# schematic.net
KiCad netlist of a schematic drawn in Altium Designer
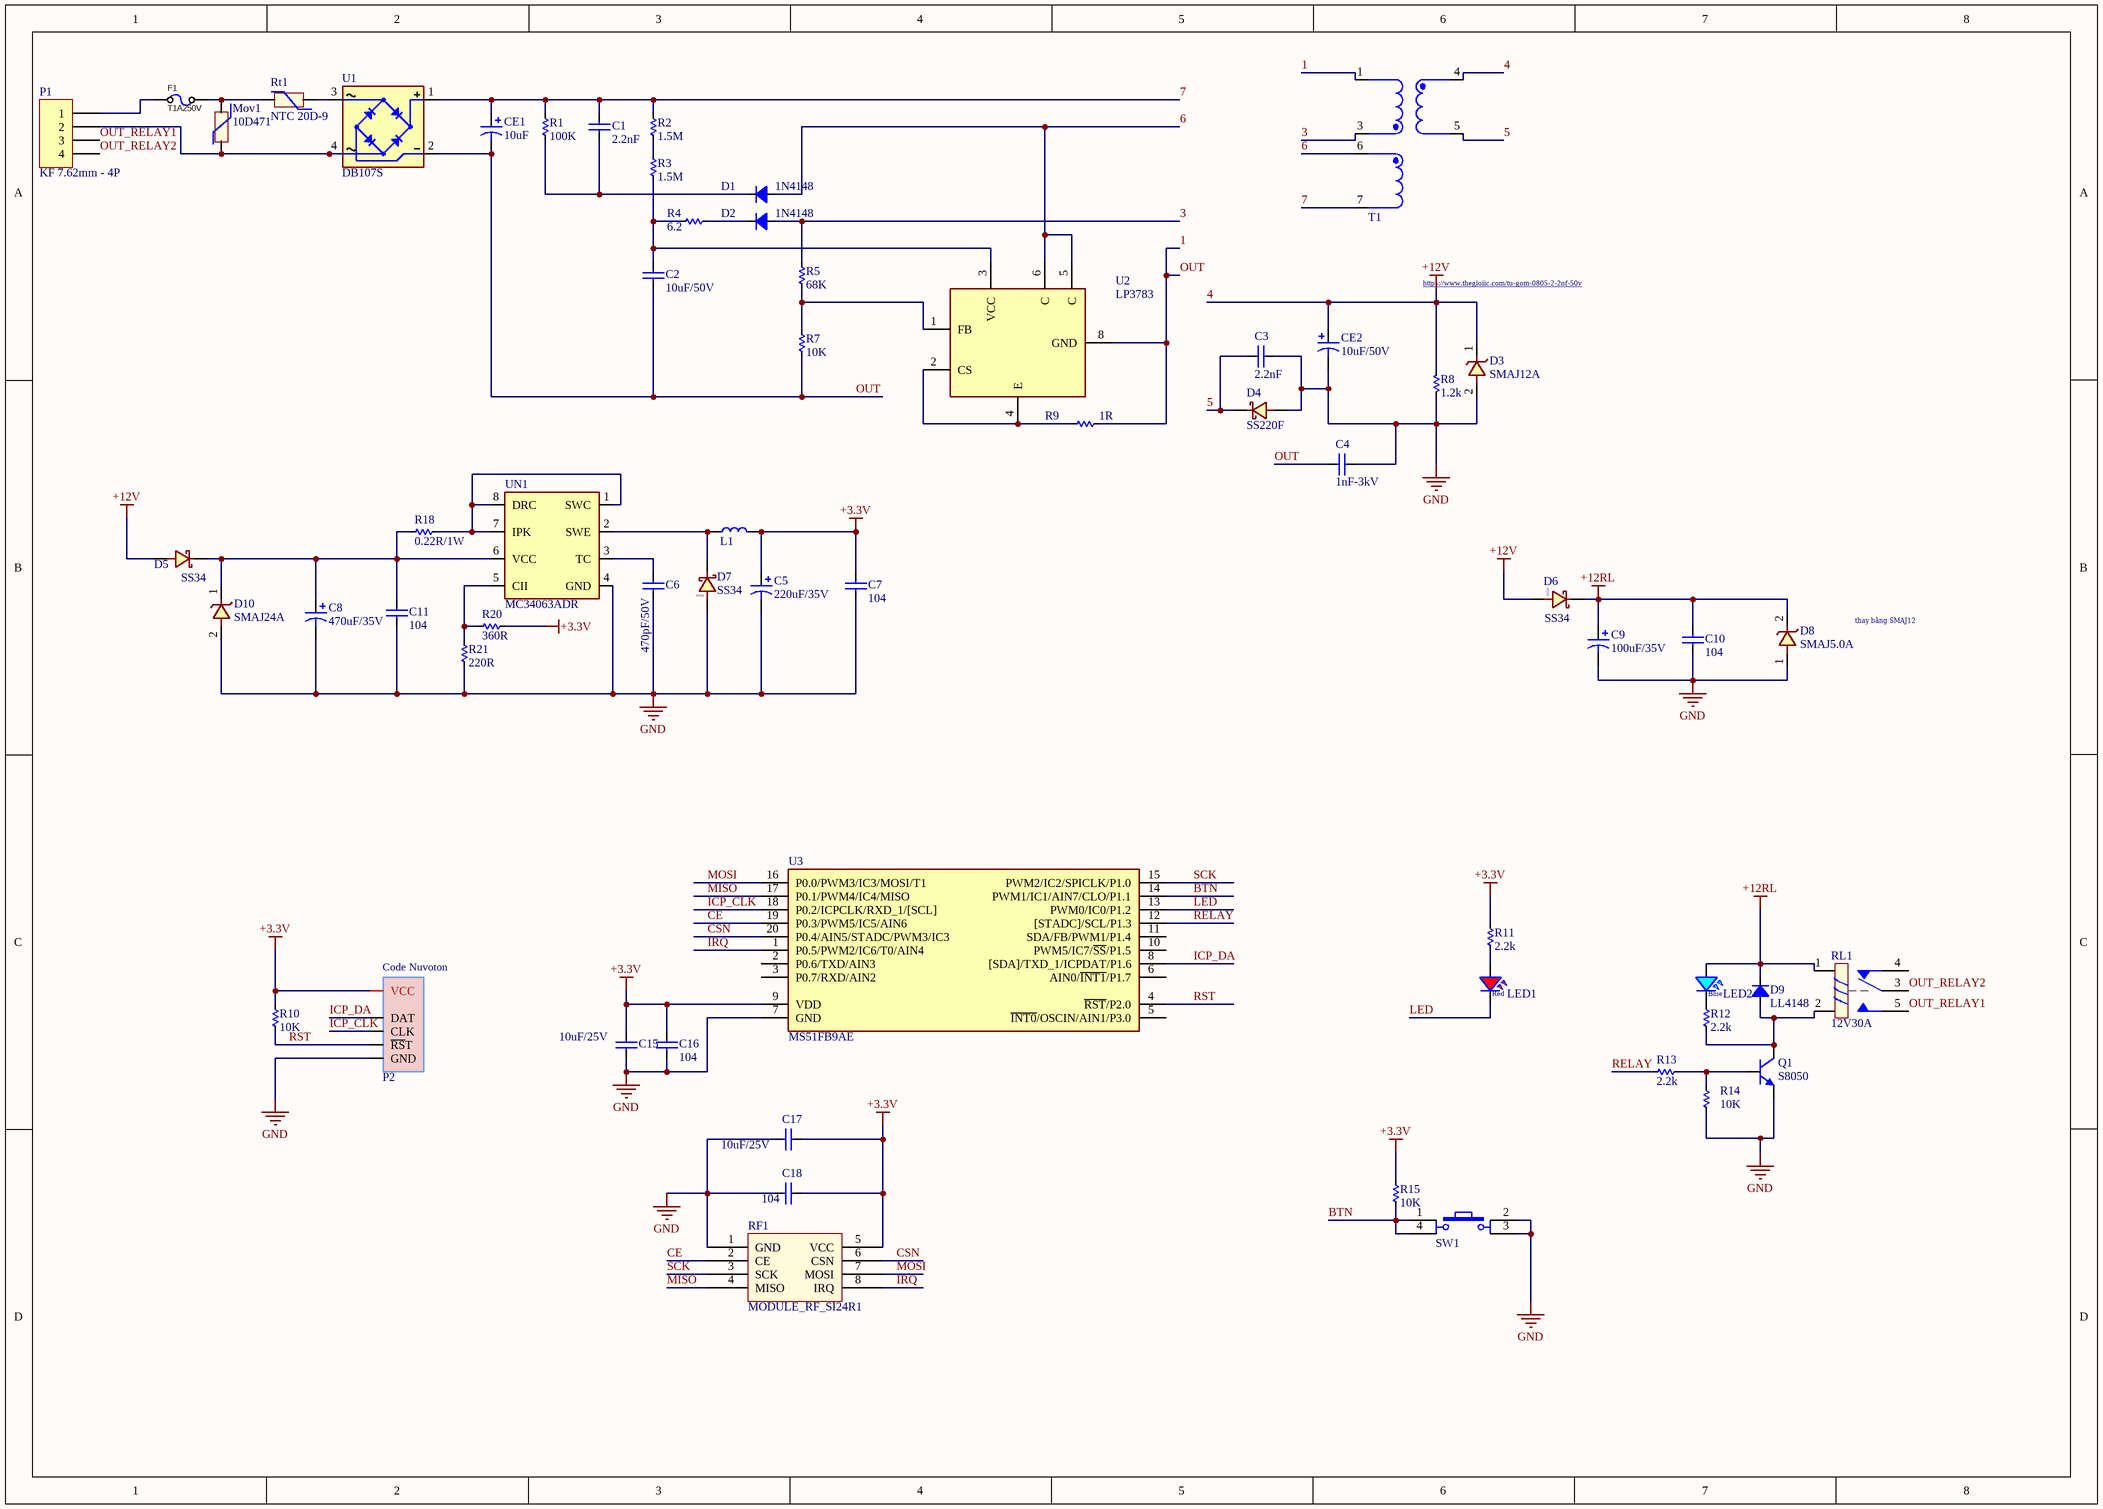
[diagram p0: schematic.SchDoc]

(export (version "E")
  (design (tool "Eeschema 10.0.6"))
  (components
    (comp (ref "C1")
      (value "2.2nF")
      (footprint "C_0805_SMD")
      (description "Tu 2.2nF 50V, SMD 0805")
      (libsource (lib "RD Integrated_Library") (part "Cap 0805 2.2nF 50V"))
    )
    (comp (ref "C2")
      (value "10uF/50V")
      (footprint "C_0805_SMD")
      (description "Cap SMD 0805 10uF 50V")
      (libsource (lib "RD Integrated_Library") (part "Cap 0805 10uF 50V"))
    )
    (comp (ref "C3")
      (value "2.2nF")
      (footprint "C_0805_SMD")
      (description "Tu 2.2nF 50V, SMD 0805")
      (libsource (lib "RD Integrated_Library") (part "Cap 0805 2.2nF 50V"))
    )
    (comp (ref "C4")
      (value "1nF-3kV")
      (footprint "CAP_CERAMIC d5.08")
      (description "102 1KV High Voltage Ceramic Disk Capacitor")
      (libsource (lib "RD Integrated_Library") (part "Cap 1nF 1KV"))
    )
    (comp (ref "C5")
      (value "220uF/35V")
      (footprint "C8X12mm")
      (description "Polarized Capacitor (Axial) 220uF 35V")
      (libsource (lib "RD Integrated_Library") (part "Cap Pol 220uF/35V"))
    )
    (comp (ref "C6")
      (value "470pF/50V")
      (footprint "C_0805_SMD")
      (description "Cap SMD 0805  470pF 50V")
      (libsource (lib "RD Integrated_Library") (part "Cap 0805 470pF 50V"))
    )
    (comp (ref "C7")
      (value "104")
      (footprint "C_0805_SMD")
      (description "Cap SMD 0805 104-100nF-0.1uF 50V")
      (libsource (lib "RD Integrated_Library") (part "Cap 0805 104 100nF"))
    )
    (comp (ref "C8")
      (value "470uF/35V")
      (footprint "C10mm")
      (description "Polarized Capacitor (Axial) 470uF 35V")
      (libsource (lib "RD Integrated_Library") (part "Cap Pol 470uF/35V"))
    )
    (comp (ref "C9")
      (value "100uF/35V")
      (footprint "C_6.3x12")
      (description "Polarized Capacitor (Axial) 100uF 35V")
      (libsource (lib "RD Integrated_Library") (part "Cap Pol 100uF/35V"))
    )
    (comp (ref "C10")
      (value "104")
      (footprint "C_0805_SMD")
      (description "Cap SMD 0805 104-100nF-0.1uF 50V")
      (libsource (lib "RD Integrated_Library") (part "Cap 0805 104 100nF"))
    )
    (comp (ref "C11")
      (value "104")
      (footprint "C_0805_SMD")
      (description "Cap SMD 0805 104-100nF-0.1uF 50V")
      (libsource (lib "RD Integrated_Library") (part "Cap 0805 104 100nF"))
    )
    (comp (ref "C15")
      (value "10uF/25V")
      (footprint "C_0805_SMD")
      (description "Cap SMD 0805 10uF")
      (libsource (lib "RD Integrated_Library") (part "Cap 0805 10uF 25V"))
    )
    (comp (ref "C16")
      (value "104")
      (footprint "C_0805_SMD")
      (description "Cap SMD 0805 104-100nF-0.1uF 50V")
      (libsource (lib "RD Integrated_Library") (part "Cap 0805 104 100nF"))
    )
    (comp (ref "C17")
      (value "10uF/25V")
      (footprint "C_0805_SMD")
      (description "Cap SMD 0805 10uF")
      (libsource (lib "RD Integrated_Library") (part "Cap 0805 10uF 25V"))
    )
    (comp (ref "C18")
      (value "104")
      (footprint "C_0805_SMD")
      (description "Cap SMD 0805 104-100nF-0.1uF 50V")
      (libsource (lib "RD Integrated_Library") (part "Cap 0805 104 100nF"))
    )
    (comp (ref "CE1")
      (value "10uF")
      (footprint "C_8X12")
      (description "Polarized Capacitor (Axial)")
      (libsource (lib "RD Integrated_Library") (part "Cap Pol 10uF 400V"))
    )
    (comp (ref "CE2")
      (value "10uF/50V")
      (footprint "C5mm")
      (description "Polarized Capacitor (Axial) 10uF/50V")
      (libsource (lib "RD Integrated_Library") (part "Cap Pol 10uF/50V"))
    )
    (comp (ref "D1")
      (value "1N4148")
      (footprint "D_SOD323")
      (description "T4-Rectifier Diode Small Signal Switching 100V 0.25A 4ns 2-Pin SOD-323")
      (libsource (lib "RD Integrated_Library") (part "1N4148WS - T4 SOD-323"))
    )
    (comp (ref "D2")
      (value "1N4148")
      (footprint "D_SOD323")
      (description "T4-Rectifier Diode Small Signal Switching 100V 0.25A 4ns 2-Pin SOD-323")
      (libsource (lib "RD Integrated_Library") (part "1N4148WS - T4 SOD-323"))
    )
    (comp (ref "D3")
      (value "SMAJ12A")
      (footprint "DO_241AC_SMA_MFG")
      (description "SMAJ12A Series 400 W 12 V Surface Mount Uni-Directional TVS Diode - DO-214AC")
      (fields (field (name "DESIGNED BY") "TranLuyen"))
      (libsource (lib "RD Integrated_Library") (part "TVS SMAJ12A-DO241AC"))
    )
    (comp (ref "D4")
      (value "SS220F")
      (footprint "D_SMA")
      (description "200V Independent Type 950mV@2A 2A SMAF Schottky Diodes ROHS")
      (libsource (lib "RD Integrated_Library") (part "SS220F-SMAF"))
    )
    (comp (ref "D5")
      (value "SS34")
      (footprint "D_SMA")
      (description "Surface-Mount Schottky Barrier Rectifier")
      (libsource (lib "RD Integrated_Library") (part "SS34-SMA"))
    )
    (comp (ref "D6")
      (value "SS34")
      (footprint "D_SMA")
      (description "Surface-Mount Schottky Barrier Rectifier")
      (libsource (lib "RD Integrated_Library") (part "SS34-SMA"))
    )
    (comp (ref "D7")
      (value "SS34")
      (footprint "D_SMA")
      (description "Surface-Mount Schottky Barrier Rectifier")
      (libsource (lib "RD Integrated_Library") (part "SS34-SMA"))
    )
    (comp (ref "D8")
      (value "SMAJ5.0A")
      (footprint "D_SMA")
      (description "SMAJ5.0A Series 400 W 5 V Surface Mount Uni-Directional TVS Diode - DO-214AC")
      (fields (field (name "DESIGNED BY") "TranLuyen"))
      (libsource (lib "RD Integrated_Library") (part "TVS SMAJ5_0A-E3-61-DO241AC"))
    )
    (comp (ref "D9")
      (value "LL4148")
      (footprint "SOD80C_MFG")
      (description "0.2A, 100V, SOD80")
      (fields (field (name "DESIGNED BY") "Nhox"))
      (libsource (lib "RD Integrated_Library") (part "LL4148"))
    )
    (comp (ref "D10")
      (value "SMAJ24A")
      (footprint "DO_241AC_SMA_MFG")
      (description "SMAJ Series 400W Surface Mount Uni-Directional TVS Diode - DO-214AC")
      (fields (field (name "DESIGNED BY") "TranLuyen"))
      (libsource (lib "RD Integrated_Library") (part "TVS SMAJ24A-DO241AC"))
    )
    (comp (ref "F1")
      (value "T1A250V")
      (footprint "Fuse 392")
      (libsource (lib "RD Integrated_Library") (part "FUSE 392 T1A250V"))
    )
    (comp (ref "L1")
      (value "220uH")
      (footprint "CDRH74")
      (description "INDUCTOR SMD")
      (libsource (lib "RD Integrated_Library") (part "CD74 7345-221 220uH"))
    )
    (comp (ref "LED1")
      (value "LED D5 Red")
      (footprint "LED 5mm RED")
      (description "LED Single colour")
      (libsource (lib "RD Integrated_Library") (part "LED 5mm RED"))
    )
    (comp (ref "LED2")
      (value "LED D5 Blue")
      (footprint "LED 5MM BLUE")
      (description "LED Single colour")
      (libsource (lib "RD Integrated_Library") (part "LED 5mm Blue"))
    )
    (comp (ref "Mov1")
      (value "10D471")
      (footprint "MOV-10D471")
      (description "MOV-10DxxxK Series - Metal Oxide Varistor")
      (fields (field (name "DESIGNED BY") "TranLuyen"))
      (libsource (lib "RD Integrated_Library") (part "Varistor 10D471K 470V"))
    )
    (comp (ref "P1")
      (value "KF 7.62mm - 4P")
      (footprint "KF 7.62 - 4")
      (fields (field (name "DESIGNED BY") "Tran Luyen"))
      (libsource (lib "RD Integrated_Library") (part "KF 7.62 - 4Pin"))
    )
    (comp (ref "P2")
      (value "Nuvoton")
      (footprint "Header Code Nuvoton 2.54 6P")
      (description "Header 6-5Pin")
      (libsource (lib "RD Integrated_Library") (part "Header Code Nuvoton"))
    )
    (comp (ref "Q1")
      (value "S8050")
      (footprint "SOT23_N NXP")
      (description "J3Y-NPN SMD Transistor SOT23")
      (libsource (lib "RD Integrated_Library") (part "S8050 SOT-23"))
    )
    (comp (ref "R1")
      (value "100K")
      (footprint "RES-SMD-0805")
      (description "Resistor SMD 0805")
      (libsource (lib "RD Integrated_Library") (part "Res 100k 0805"))
    )
    (comp (ref "R2")
      (value "1.5M")
      (footprint "RES-SMD-0805")
      (description "Resistor SMD 0805")
      (libsource (lib "RD Integrated_Library") (part "Res 1.5M 0805"))
    )
    (comp (ref "R3")
      (value "1.5M")
      (footprint "RES-SMD-0805")
      (description "Resistor SMD 0805")
      (libsource (lib "RD Integrated_Library") (part "Res 1.5M 0805"))
    )
    (comp (ref "R4")
      (value "6.2")
      (footprint "RES-SMD-0805")
      (description "Resistor SMD 0805")
      (libsource (lib "RD Integrated_Library") (part "Res 6.2 0805"))
    )
    (comp (ref "R5")
      (value "68K")
      (footprint "RES-SMD-0805")
      (description "Resistor SMD 0805")
      (libsource (lib "RD Integrated_Library") (part "Res 68K 0805"))
    )
    (comp (ref "R7")
      (value "10K")
      (footprint "RES-SMD-0805")
      (description "Resistor SMD 0805")
      (libsource (lib "RD Integrated_Library") (part "Res 10k 0805"))
    )
    (comp (ref "R8")
      (value "1.2k")
      (footprint "RES-SMD-0805")
      (description "Resistor SMD 0805")
      (libsource (lib "RD Integrated_Library") (part "Res 1.2k 0805"))
    )
    (comp (ref "R9")
      (value "1R")
      (footprint "RES-SMD-1206")
      (description "Resistor SMD 1206")
      (libsource (lib "RD Integrated_Library") (part "Res 1R 1206"))
    )
    (comp (ref "R10")
      (value "10K")
      (footprint "RES-SMD-0805")
      (description "Resistor SMD 0805")
      (libsource (lib "RD Integrated_Library") (part "Res 10k 0805"))
    )
    (comp (ref "R11")
      (value "2.2k")
      (footprint "RES-SMD-0805")
      (description "Resistor SMD 0805")
      (libsource (lib "RD Integrated_Library") (part "Res 2.2K 0805"))
    )
    (comp (ref "R12")
      (value "2.2k")
      (footprint "RES-SMD-0805")
      (description "Resistor SMD 0805")
      (libsource (lib "RD Integrated_Library") (part "Res 2.2K 0805"))
    )
    (comp (ref "R13")
      (value "2.2k")
      (footprint "RES-SMD-0805")
      (description "Resistor SMD 0805")
      (libsource (lib "RD Integrated_Library") (part "Res 2.2K 0805"))
    )
    (comp (ref "R14")
      (value "10K")
      (footprint "RES-SMD-0805")
      (description "Resistor SMD 0805")
      (libsource (lib "RD Integrated_Library") (part "Res 10k 0805"))
    )
    (comp (ref "R15")
      (value "10K")
      (footprint "RES-SMD-0805")
      (description "Resistor SMD 0805")
      (libsource (lib "RD Integrated_Library") (part "Res 10k 0805"))
    )
    (comp (ref "R18")
      (value "0.22R/1W")
      (footprint "RES-SMD-2512")
      (description "Resistor SMD 2512 1W")
      (libsource (lib "RD Integrated_Library") (part "Res 0.22R 2512 1W"))
    )
    (comp (ref "R20")
      (value "360R")
      (footprint "RES-SMD-0805")
      (description "Resistor SMD 0805")
      (libsource (lib "RD Integrated_Library") (part "Res 360R 0805"))
    )
    (comp (ref "R21")
      (value "220R")
      (footprint "RES-SMD-0805")
      (description "Resistor SMD 0805")
      (libsource (lib "RD Integrated_Library") (part "Res 220R 0805"))
    )
    (comp (ref "RF1")
      (value "MODULE_RF_SI24R1")
      (footprint "MODULE-RF-Si24R1")
      (libsource (lib "RD Integrated_Library") (part "MODULE RF SI24R1"))
    )
    (comp (ref "RL1")
      (value "12V30A")
      (footprint "Relay 30A 5 Pin")
      (description "Relay SLA-12VDC-SL-A-30A 5P")
      (libsource (lib "RD Integrated_Library") (part "Relay SLA-12VDC-SL-A-30A 5P"))
    )
    (comp (ref "Rt1")
      (value "NTC 20D-9")
      (footprint "NTC 5D-9")
      (description "NTC Thermistor")
      (libsource (lib "RD Integrated_Library") (part "NTC 20D-9"))
    )
    (comp (ref "SW1")
      (value "BT4")
      (footprint "SW4-DIP 6x6x12")
      (description "Switch button 4 pin 6x6 mm DIP")
      (fields (field (name "DESIGNED BY") "TranLuyen"))
      (libsource (lib "RD Integrated_Library") (part "SW4 DIP 6x6x12mm"))
    )
    (comp (ref "T1")
      (value "24V-7VA")
      (footprint "EE15")
      (description "Transformer EE15 6 PIN")
      (libsource (lib "RD Integrated_Library") (part "TRANS EE15 5V-2A"))
    )
    (comp (ref "U1")
      (value "DB107S")
      (footprint "DBRG_DIPSMD_MINI")
      (description "BRIDGE RECTIFIER 1KV 1A")
      (fields (field (name "DESIGNED BY") "TranLuyen"))
      (libsource (lib "RD Integrated_Library") (part "MB10F 1KV 0.5A"))
    )
    (comp (ref "U2")
      (value "LP3783")
      (footprint "SO_8")
      (libsource (lib "RD Integrated_Library") (part "LP3783"))
    )
    (comp (ref "U3")
      (value "MS51FB9AE")
      (footprint "SOG65_20")
      (description "MS51FB9AE, ROM 16KB, RAM 256B + 1KB, SPROM 128B, 1T 8051-based CMOS up to 24Mhz")
      (fields (field (name "DESIGNED BY") "Nhox"))
      (libsource (lib "RD Integrated_Library") (part "MS51FB9AE"))
    )
    (comp (ref "UN1")
      (value "MC34063ADR")
      (footprint "SO_8")
      (description "MC3x063A 1.5-A Peak Boost/Buck/Inverting Switching Regulators")
      (fields (field (name "DESIGNED BY") "TranLuyen"))
      (libsource (lib "RD Integrated_Library") (part "MC34063ADR"))
    )
  )
  (nets
    (net (code "1") (name "+3.3V") (class "Default")
      (node (ref "C15") (pin "1") (pinfunction "1_1") (pintype "passive"))
      (node (ref "C16") (pin "1") (pinfunction "1_1") (pintype "passive"))
      (node (ref "C17") (pin "2") (pinfunction "2_2") (pintype "passive"))
      (node (ref "C18") (pin "1") (pinfunction "1_1") (pintype "passive"))
      (node (ref "C5") (pin "1") (pinfunction "1_1") (pintype "passive"))
      (node (ref "C7") (pin "1") (pinfunction "1_1") (pintype "passive"))
      (node (ref "L1") (pin "2") (pinfunction "2_2") (pintype "passive"))
      (node (ref "P2") (pin "1") (pinfunction "VCC_1") (pintype "passive"))
      (node (ref "R10") (pin "1") (pinfunction "1_1") (pintype "passive"))
      (node (ref "R11") (pin "1") (pinfunction "1_1") (pintype "passive"))
      (node (ref "R15") (pin "1") (pinfunction "1_1") (pintype "passive"))
      (node (ref "R20") (pin "1") (pinfunction "1_1") (pintype "passive"))
      (node (ref "RF1") (pin "5") (pinfunction "VCC_5") (pintype "passive"))
      (node (ref "U3") (pin "9") (pinfunction "VDD_9") (pintype "passive"))
    )
    (net (code "2") (name "+12RL") (class "Default")
      (node (ref "C10") (pin "1") (pinfunction "1_1") (pintype "passive"))
      (node (ref "C9") (pin "1") (pinfunction "1_1") (pintype "passive"))
      (node (ref "D6") (pin "2") (pinfunction "K_2") (pintype "passive"))
      (node (ref "D8") (pin "2") (pinfunction "2_2") (pintype "passive"))
      (node (ref "D9") (pin "1") (pinfunction "1_1") (pintype "passive"))
      (node (ref "LED2") (pin "1") (pinfunction "1_1") (pintype "passive"))
      (node (ref "RL1") (pin "1") (pinfunction "1_1") (pintype "passive"))
    )
    (net (code "3") (name "+12V") (class "Default")
      (node (ref "CE2") (pin "1") (pinfunction "1_1") (pintype "passive"))
      (node (ref "D3") (pin "1") (pinfunction "1_1") (pintype "passive"))
      (node (ref "D5") (pin "1") (pinfunction "A_1") (pintype "passive"))
      (node (ref "D6") (pin "1") (pinfunction "A_1") (pintype "passive"))
      (node (ref "R8") (pin "1") (pinfunction "1_1") (pintype "passive"))
      (node (ref "T1") (pin "4") (pinfunction "4_4") (pintype "passive"))
    )
    (net (code "4") (name "/1") (class "Default")
      (node (ref "C2") (pin "2") (pinfunction "2_2") (pintype "passive"))
      (node (ref "C4") (pin "2") (pinfunction "2_2") (pintype "passive"))
      (node (ref "CE1") (pin "2") (pinfunction "2_2") (pintype "passive"))
      (node (ref "R7") (pin "2") (pinfunction "2_2") (pintype "passive"))
      (node (ref "R9") (pin "2") (pinfunction "2_2") (pintype "passive"))
      (node (ref "T1") (pin "1") (pinfunction "1_1") (pintype "passive"))
      (node (ref "U1") (pin "2") (pinfunction "DCOUT-_2") (pintype "passive"))
      (node (ref "U2") (pin "8") (pinfunction "GND_8") (pintype "passive"))
    )
    (net (code "5") (name "/3") (class "Default")
      (node (ref "D2") (pin "1") (pinfunction "1_1") (pintype "passive"))
      (node (ref "R5") (pin "1") (pinfunction "1_1") (pintype "passive"))
      (node (ref "T1") (pin "3") (pinfunction "3_3") (pintype "passive"))
    )
    (net (code "6") (name "/5") (class "Default")
      (node (ref "C3") (pin "1") (pinfunction "1_1") (pintype "passive"))
      (node (ref "D4") (pin "2") (pinfunction "K_2") (pintype "passive"))
      (node (ref "T1") (pin "5") (pinfunction "5_5") (pintype "passive"))
    )
    (net (code "7") (name "/6") (class "Default")
      (node (ref "D1") (pin "1") (pinfunction "1_1") (pintype "passive"))
      (node (ref "T1") (pin "6") (pinfunction "6_6") (pintype "passive"))
      (node (ref "U2") (pin "5") (pinfunction "C_5") (pintype "passive"))
      (node (ref "U2") (pin "6") (pinfunction "C_6") (pintype "passive"))
    )
    (net (code "8") (name "/7") (class "Default")
      (node (ref "C1") (pin "2") (pinfunction "2_2") (pintype "passive"))
      (node (ref "CE1") (pin "1") (pinfunction "1_1") (pintype "passive"))
      (node (ref "R1") (pin "1") (pinfunction "1_1") (pintype "passive"))
      (node (ref "R2") (pin "1") (pinfunction "1_1") (pintype "passive"))
      (node (ref "T1") (pin "7") (pinfunction "7_7") (pintype "passive"))
      (node (ref "U1") (pin "1") (pinfunction "DCOUT+_1") (pintype "passive"))
    )
    (net (code "9") (name "/BTN") (class "Default")
      (node (ref "R15") (pin "2") (pinfunction "2_2") (pintype "passive"))
      (node (ref "SW1") (pin "1") (pintype "passive"))
      (node (ref "SW1") (pin "4") (pintype "passive"))
      (node (ref "U3") (pin "14") (pinfunction "PWM1/IC1/AIN7/CLO/P1.1_14") (pintype "passive"))
    )
    (net (code "10") (name "/CE") (class "Default")
      (node (ref "RF1") (pin "2") (pinfunction "CE_2") (pintype "passive"))
      (node (ref "U3") (pin "19") (pinfunction "P0.3/PWM5/IC5/AIN6_19") (pintype "passive"))
    )
    (net (code "11") (name "/CSN") (class "Default")
      (node (ref "RF1") (pin "6") (pinfunction "CSN_6") (pintype "passive"))
      (node (ref "U3") (pin "20") (pinfunction "P0.4/AIN5/STADC/PWM3/IC3_20") (pintype "passive"))
    )
    (net (code "12") (name "/ICP_CLK") (class "Default")
      (node (ref "P2") (pin "4") (pinfunction "CLK_4") (pintype "passive"))
      (node (ref "U3") (pin "18") (pinfunction "P0.2/ICPCLK/RXD_1/[SCL]_18") (pintype "passive"))
    )
    (net (code "13") (name "/ICP_DA") (class "Default")
      (node (ref "P2") (pin "3") (pinfunction "DAT_3") (pintype "passive"))
      (node (ref "U3") (pin "8") (pinfunction "[SDA]/TXD_1/ICPDAT/P1.6_8") (pintype "passive"))
    )
    (net (code "14") (name "/IRQ") (class "Default")
      (node (ref "RF1") (pin "8") (pinfunction "IRQ_8") (pintype "passive"))
      (node (ref "U3") (pin "1") (pinfunction "P0.5/PWM2/IC6/T0/AIN4_1") (pintype "passive"))
    )
    (net (code "15") (name "/LED") (class "Default")
      (node (ref "LED1") (pin "2") (pinfunction "2_2") (pintype "passive"))
      (node (ref "U3") (pin "13") (pinfunction "PWM0/IC0/P1.2_13") (pintype "passive"))
    )
    (net (code "16") (name "/MISO") (class "Default")
      (node (ref "RF1") (pin "4") (pinfunction "MISO_4") (pintype "passive"))
      (node (ref "U3") (pin "17") (pinfunction "P0.1/PWM4/IC4/MISO_17") (pintype "passive"))
    )
    (net (code "17") (name "/MOSI") (class "Default")
      (node (ref "RF1") (pin "7") (pinfunction "MOSI_7") (pintype "passive"))
      (node (ref "U3") (pin "16") (pinfunction "P0.0/PWM3/IC3/MOSI/T1_16") (pintype "passive"))
    )
    (net (code "18") (name "/OUT_RELAY1") (class "Default")
      (node (ref "P1") (pin "3") (pinfunction "3_3") (pintype "passive"))
      (node (ref "RL1") (pin "5") (pinfunction "5_5") (pintype "passive"))
    )
    (net (code "19") (name "/OUT_RELAY2") (class "Default")
      (node (ref "P1") (pin "4") (pinfunction "4_4") (pintype "passive"))
      (node (ref "RL1") (pin "3") (pinfunction "3_3") (pintype "passive"))
    )
    (net (code "20") (name "/RELAY") (class "Default")
      (node (ref "R13") (pin "2") (pinfunction "2_2") (pintype "passive"))
      (node (ref "U3") (pin "12") (pinfunction "[STADC]/SCL/P1.3_12") (pintype "passive"))
    )
    (net (code "21") (name "/RST") (class "Default")
      (node (ref "P2") (pin "5") (pinfunction "~{RS}T_5") (pintype "passive"))
      (node (ref "R10") (pin "2") (pinfunction "2_2") (pintype "passive"))
      (node (ref "U3") (pin "4") (pinfunction "~{RST}/P2.0_4") (pintype "passive"))
    )
    (net (code "22") (name "/SCK") (class "Default")
      (node (ref "RF1") (pin "3") (pinfunction "SCK_3") (pintype "passive"))
      (node (ref "U3") (pin "15") (pinfunction "PWM2/IC2/SPICLK/P1.0_15") (pintype "passive"))
    )
    (net (code "23") (name "GND") (class "Default")
      (node (ref "C10") (pin "2") (pinfunction "2_2") (pintype "passive"))
      (node (ref "C11") (pin "1") (pinfunction "1_1") (pintype "passive"))
      (node (ref "C15") (pin "2") (pinfunction "2_2") (pintype "passive"))
      (node (ref "C16") (pin "2") (pinfunction "2_2") (pintype "passive"))
      (node (ref "C17") (pin "1") (pinfunction "1_1") (pintype "passive"))
      (node (ref "C18") (pin "2") (pinfunction "2_2") (pintype "passive"))
      (node (ref "C3") (pin "2") (pinfunction "2_2") (pintype "passive"))
      (node (ref "C4") (pin "1") (pinfunction "1_1") (pintype "passive"))
      (node (ref "C5") (pin "2") (pinfunction "2_2") (pintype "passive"))
      (node (ref "C6") (pin "1") (pinfunction "1_1") (pintype "passive"))
      (node (ref "C7") (pin "2") (pinfunction "2_2") (pintype "passive"))
      (node (ref "C8") (pin "2") (pinfunction "2_2") (pintype "passive"))
      (node (ref "C9") (pin "2") (pinfunction "2_2") (pintype "passive"))
      (node (ref "CE2") (pin "2") (pinfunction "2_2") (pintype "passive"))
      (node (ref "D10") (pin "2") (pinfunction "2_2") (pintype "passive"))
      (node (ref "D3") (pin "2") (pinfunction "2_2") (pintype "passive"))
      (node (ref "D4") (pin "1") (pinfunction "A_1") (pintype "passive"))
      (node (ref "D7") (pin "1") (pinfunction "A_1") (pintype "passive"))
      (node (ref "D8") (pin "1") (pinfunction "1_1") (pintype "passive"))
      (node (ref "P2") (pin "6") (pinfunction "GND_6") (pintype "passive"))
      (node (ref "Q1") (pin "2") (pinfunction "E_2") (pintype "passive"))
      (node (ref "R14") (pin "1") (pinfunction "1_1") (pintype "passive"))
      (node (ref "R21") (pin "2") (pinfunction "2_2") (pintype "passive"))
      (node (ref "R8") (pin "2") (pinfunction "2_2") (pintype "passive"))
      (node (ref "RF1") (pin "1") (pinfunction "GND_1") (pintype "passive"))
      (node (ref "SW1") (pin "2") (pintype "passive"))
      (node (ref "SW1") (pin "3") (pintype "passive"))
      (node (ref "U3") (pin "7") (pinfunction "GND_7") (pintype "passive"))
      (node (ref "UN1") (pin "4") (pinfunction "GND_4") (pintype "passive"))
    )
    (net (code "24") (name "Net-(C1-Pad1)") (class "Default")
      (node (ref "C1") (pin "1") (pinfunction "1_1") (pintype "passive"))
      (node (ref "D1") (pin "2") (pinfunction "2_2") (pintype "passive"))
      (node (ref "R1") (pin "2") (pinfunction "2_2") (pintype "passive"))
    )
    (net (code "25") (name "Net-(D2-Pad2)") (class "Default")
      (node (ref "D2") (pin "2") (pinfunction "2_2") (pintype "passive"))
      (node (ref "R4") (pin "2") (pinfunction "2_2") (pintype "passive"))
    )
    (net (code "26") (name "Net-(D5-K)") (class "Default")
      (node (ref "C11") (pin "2") (pinfunction "2_2") (pintype "passive"))
      (node (ref "C8") (pin "1") (pinfunction "1_1") (pintype "passive"))
      (node (ref "D10") (pin "1") (pinfunction "1_1") (pintype "passive"))
      (node (ref "D5") (pin "2") (pinfunction "K_2") (pintype "passive"))
      (node (ref "R18") (pin "2") (pinfunction "2_2") (pintype "passive"))
      (node (ref "UN1") (pin "6") (pinfunction "VCC_6") (pintype "passive"))
    )
    (net (code "27") (name "Net-(D7-K)") (class "Default")
      (node (ref "D7") (pin "2") (pinfunction "K_2") (pintype "passive"))
      (node (ref "L1") (pin "1") (pinfunction "1_1") (pintype "passive"))
      (node (ref "UN1") (pin "2") (pinfunction "SWE_2") (pintype "passive"))
    )
    (net (code "28") (name "Net-(F1-Pad1)") (class "Default")
      (node (ref "F1") (pin "1") (pinfunction "1_1") (pintype "passive"))
      (node (ref "P1") (pin "1") (pinfunction "1_1") (pintype "passive"))
    )
    (net (code "29") (name "Net-(F1-Pad2)") (class "Default")
      (node (ref "F1") (pin "2") (pinfunction "2_2") (pintype "passive"))
      (node (ref "Mov1") (pin "1") (pinfunction "1_1") (pintype "passive"))
      (node (ref "Rt1") (pin "2") (pinfunction "2_2") (pintype "passive"))
    )
    (net (code "30") (name "Net-(LED1-Pad1)") (class "Default")
      (node (ref "LED1") (pin "1") (pinfunction "1_1") (pintype "passive"))
      (node (ref "R11") (pin "2") (pinfunction "2_2") (pintype "passive"))
    )
    (net (code "31") (name "Net-(LED2-Pad2)") (class "Default")
      (node (ref "LED2") (pin "2") (pinfunction "2_2") (pintype "passive"))
      (node (ref "R12") (pin "1") (pinfunction "1_1") (pintype "passive"))
    )
    (net (code "32") (name "Net-(Q1-B)") (class "Default")
      (node (ref "Q1") (pin "1") (pinfunction "B_1") (pintype "passive"))
      (node (ref "R13") (pin "1") (pinfunction "1_1") (pintype "passive"))
      (node (ref "R14") (pin "2") (pinfunction "2_2") (pintype "passive"))
    )
    (net (code "33") (name "Net-(Q1-C)") (class "Default")
      (node (ref "D9") (pin "2") (pinfunction "2_2") (pintype "passive"))
      (node (ref "Q1") (pin "3") (pinfunction "C_3") (pintype "passive"))
      (node (ref "R12") (pin "2") (pinfunction "2_2") (pintype "passive"))
      (node (ref "RL1") (pin "2") (pinfunction "2_2") (pintype "passive"))
    )
    (net (code "34") (name "Net-(R2-Pad2)") (class "Default")
      (node (ref "R2") (pin "2") (pinfunction "2_2") (pintype "passive"))
      (node (ref "R3") (pin "1") (pinfunction "1_1") (pintype "passive"))
    )
    (net (code "35") (name "Net-(U1-ACIN1)") (class "Default")
      (node (ref "Mov1") (pin "2") (pinfunction "2_2") (pintype "passive"))
      (node (ref "P1") (pin "2") (pinfunction "2_2") (pintype "passive"))
      (node (ref "U1") (pin "4") (pinfunction "ACIN1_4") (pintype "passive"))
    )
    (net (code "36") (name "Net-(U1-ACIN2)") (class "Default")
      (node (ref "Rt1") (pin "1") (pinfunction "1_1") (pintype "passive"))
      (node (ref "U1") (pin "3") (pinfunction "ACIN2_3") (pintype "passive"))
    )
    (net (code "37") (name "Net-(U2-CS)") (class "Default")
      (node (ref "R9") (pin "1") (pinfunction "1_1") (pintype "passive"))
      (node (ref "U2") (pin "2") (pinfunction "CS_2") (pintype "passive"))
      (node (ref "U2") (pin "4") (pinfunction "E_4") (pintype "passive"))
    )
    (net (code "38") (name "Net-(U2-FB)") (class "Default")
      (node (ref "R5") (pin "2") (pinfunction "2_2") (pintype "passive"))
      (node (ref "R7") (pin "1") (pinfunction "1_1") (pintype "passive"))
      (node (ref "U2") (pin "1") (pinfunction "FB_1") (pintype "passive"))
    )
    (net (code "39") (name "Net-(U2-VCC)") (class "Default")
      (node (ref "C2") (pin "1") (pinfunction "1_1") (pintype "passive"))
      (node (ref "R3") (pin "2") (pinfunction "2_2") (pintype "passive"))
      (node (ref "R4") (pin "1") (pinfunction "1_1") (pintype "passive"))
      (node (ref "U2") (pin "3") (pinfunction "VCC_3") (pintype "passive"))
    )
    (net (code "40") (name "Net-(UN1-CII)") (class "Default")
      (node (ref "R20") (pin "2") (pinfunction "2_2") (pintype "passive"))
      (node (ref "R21") (pin "1") (pinfunction "1_1") (pintype "passive"))
      (node (ref "UN1") (pin "5") (pinfunction "CII_5") (pintype "passive"))
    )
    (net (code "41") (name "Net-(UN1-DRC)") (class "Default")
      (node (ref "R18") (pin "1") (pinfunction "1_1") (pintype "passive"))
      (node (ref "UN1") (pin "1") (pinfunction "SWC_1") (pintype "passive"))
      (node (ref "UN1") (pin "7") (pinfunction "IPK_7") (pintype "passive"))
      (node (ref "UN1") (pin "8") (pinfunction "DRC_8") (pintype "passive"))
    )
    (net (code "42") (name "Net-(UN1-TC)") (class "Default")
      (node (ref "C6") (pin "2") (pinfunction "2_2") (pintype "passive"))
      (node (ref "UN1") (pin "3") (pinfunction "TC_3") (pintype "passive"))
    )
    (net (code "43") (name "unconnected-(RL1-Pad4)") (class "Default")
      (node (ref "RL1") (pin "4") (pinfunction "4_4") (pintype "passive"))
    )
    (net (code "44") (name "unconnected-(U3-AIN0{slash}~{INT1}{slash}P1.7-Pad6)") (class "Default")
      (node (ref "U3") (pin "6") (pinfunction "AIN0/~{INT1}/P1.7_6") (pintype "passive"))
    )
    (net (code "45") (name "unconnected-(U3-P0.6{slash}TXD{slash}AIN3-Pad2)") (class "Default")
      (node (ref "U3") (pin "2") (pinfunction "P0.6/TXD/AIN3_2") (pintype "passive"))
    )
    (net (code "46") (name "unconnected-(U3-P0.7{slash}RXD{slash}AIN2-Pad3)") (class "Default")
      (node (ref "U3") (pin "3") (pinfunction "P0.7/RXD/AIN2_3") (pintype "passive"))
    )
    (net (code "47") (name "unconnected-(U3-PWM5{slash}IC7{slash}~{SS}{slash}P1.5-Pad10)") (class "Default")
      (node (ref "U3") (pin "10") (pinfunction "PWM5/IC7/~{SS}/P1.5_10") (pintype "passive"))
    )
    (net (code "48") (name "unconnected-(U3-SDA{slash}FB{slash}PWM1{slash}P1.4-Pad11)") (class "Default")
      (node (ref "U3") (pin "11") (pinfunction "SDA/FB/PWM1/P1.4_11") (pintype "passive"))
    )
    (net (code "49") (name "unconnected-(U3-~{INT0}{slash}OSCIN{slash}AIN1{slash}P3.0-Pad5)") (class "Default")
      (node (ref "U3") (pin "5") (pinfunction "~{INT0}/OSCIN/AIN1/P3.0_5") (pintype "passive"))
    )
  )
)
